# SolarPwrOption_open.net
KiCad netlist of a schematic drawn in EAGLE
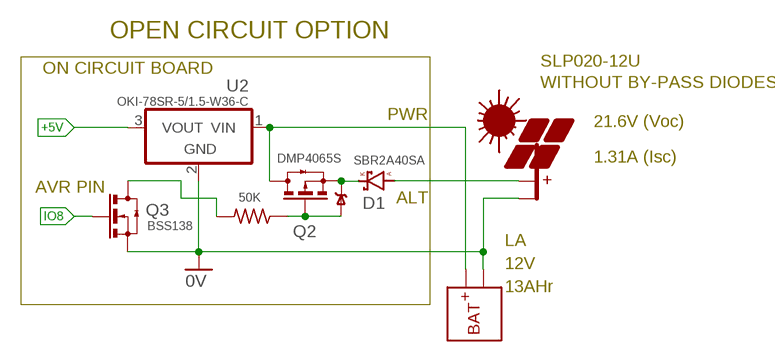
[diagram p0: schematic, sheet 1]

(export (version "E")
  (design (tool "Eeschema 10.0.6"))
  (components
    (comp (ref "D1")
      (value "SBR2A40SA")
      (footprint "eagle-import:SMB")
      (libsource (lib "eagle-import") (part "DSMB"))
    )
    (comp (ref "D3")
      (value "TVSSMC")
      (footprint "eagle-import:SMC")
      (libsource (lib "eagle-import") (part "TVSSMC"))
    )
    (comp (ref "PV2")
      (value "PV")
      (footprint "eagle-import:NA-30")
      (libsource (lib "eagle-import") (part "PV"))
    )
    (comp (ref "Q2")
      (value "DMP4065S")
      (footprint "eagle-import:DPAK")
      (libsource (lib "eagle-import") (part "Q-PCH_N-CH?DPAK"))
    )
    (comp (ref "Q3")
      (value "BSS138")
      (footprint "eagle-import:DPAK")
      (libsource (lib "eagle-import") (part "N-CH?DPAK"))
    )
    (comp (ref "R2")
      (value "50K")
      (footprint "eagle-import:C0805(2012)")
      (libsource (lib "eagle-import") (part "R0805"))
    )
    (comp (ref "U$1")
      (value "BAT")
      (footprint "eagle-import:NA-30")
      (libsource (lib "eagle-import") (part "BAT"))
    )
    (comp (ref "U2")
      (value "OKI-78SR-5/1.5-W36-C")
      (footprint "eagle-import:OKI-78SR-H")
      (libsource (lib "eagle-import") (part "OKI-78SR-H"))
    )
  )
  (nets
    (net (code "1") (name "+5V") (class "Default")
      (node (ref "U2") (pin "3") (pinfunction "VOUT_3") (pintype "passive"))
    )
    (net (code "2") (name "0V") (class "Default")
      (node (ref "PV2") (pin "2") (pinfunction "-PV_2") (pintype "bidirectional"))
      (node (ref "Q3") (pin "3") (pinfunction "S_3") (pintype "passive"))
      (node (ref "U$1") (pin "2") (pinfunction "-BAT_2") (pintype "bidirectional"))
      (node (ref "U2") (pin "2") (pinfunction "GND_2") (pintype "passive"))
    )
    (net (code "3") (name "IO8") (class "Default")
      (node (ref "Q3") (pin "1") (pinfunction "G_1") (pintype "passive"))
    )
    (net (code "4") (name "Net-(PV2-+PV)") (class "Default")
      (node (ref "D1") (pin "A") (pinfunction "A_A") (pintype "passive"))
      (node (ref "PV2") (pin "1") (pinfunction "+PV_1") (pintype "bidirectional"))
    )
    (net (code "5") (name "Net-(Q2-D)") (class "Default")
      (node (ref "Q2") (pin "SINK") (pinfunction "D_SINK") (pintype "passive"))
      (node (ref "U$1") (pin "1") (pinfunction "+BAT_1") (pintype "bidirectional"))
      (node (ref "U2") (pin "1") (pinfunction "VIN_1") (pintype "passive"))
    )
    (net (code "6") (name "Net-(Q2-G)") (class "Default")
      (node (ref "D3") (pin "A") (pinfunction "A_A") (pintype "passive"))
      (node (ref "Q2") (pin "1") (pinfunction "G_1") (pintype "passive"))
      (node (ref "R2") (pin "1") (pinfunction "1_1") (pintype "passive"))
    )
    (net (code "7") (name "Net-(Q2-S)") (class "Default")
      (node (ref "D1") (pin "K") (pinfunction "K_K") (pintype "passive"))
      (node (ref "D3") (pin "C") (pinfunction "C_C") (pintype "passive"))
      (node (ref "Q2") (pin "3") (pinfunction "S_3") (pintype "passive"))
    )
    (net (code "8") (name "Net-(Q3-D)") (class "Default")
      (node (ref "Q3") (pin "SINK") (pinfunction "D_SINK") (pintype "passive"))
      (node (ref "R2") (pin "2") (pinfunction "2_2") (pintype "passive"))
    )
  )
)
